# SCH_GroeiAcademie-Stimulus-Hardware-Shie.net
KiCad netlist of a schematic drawn in EasyEDA
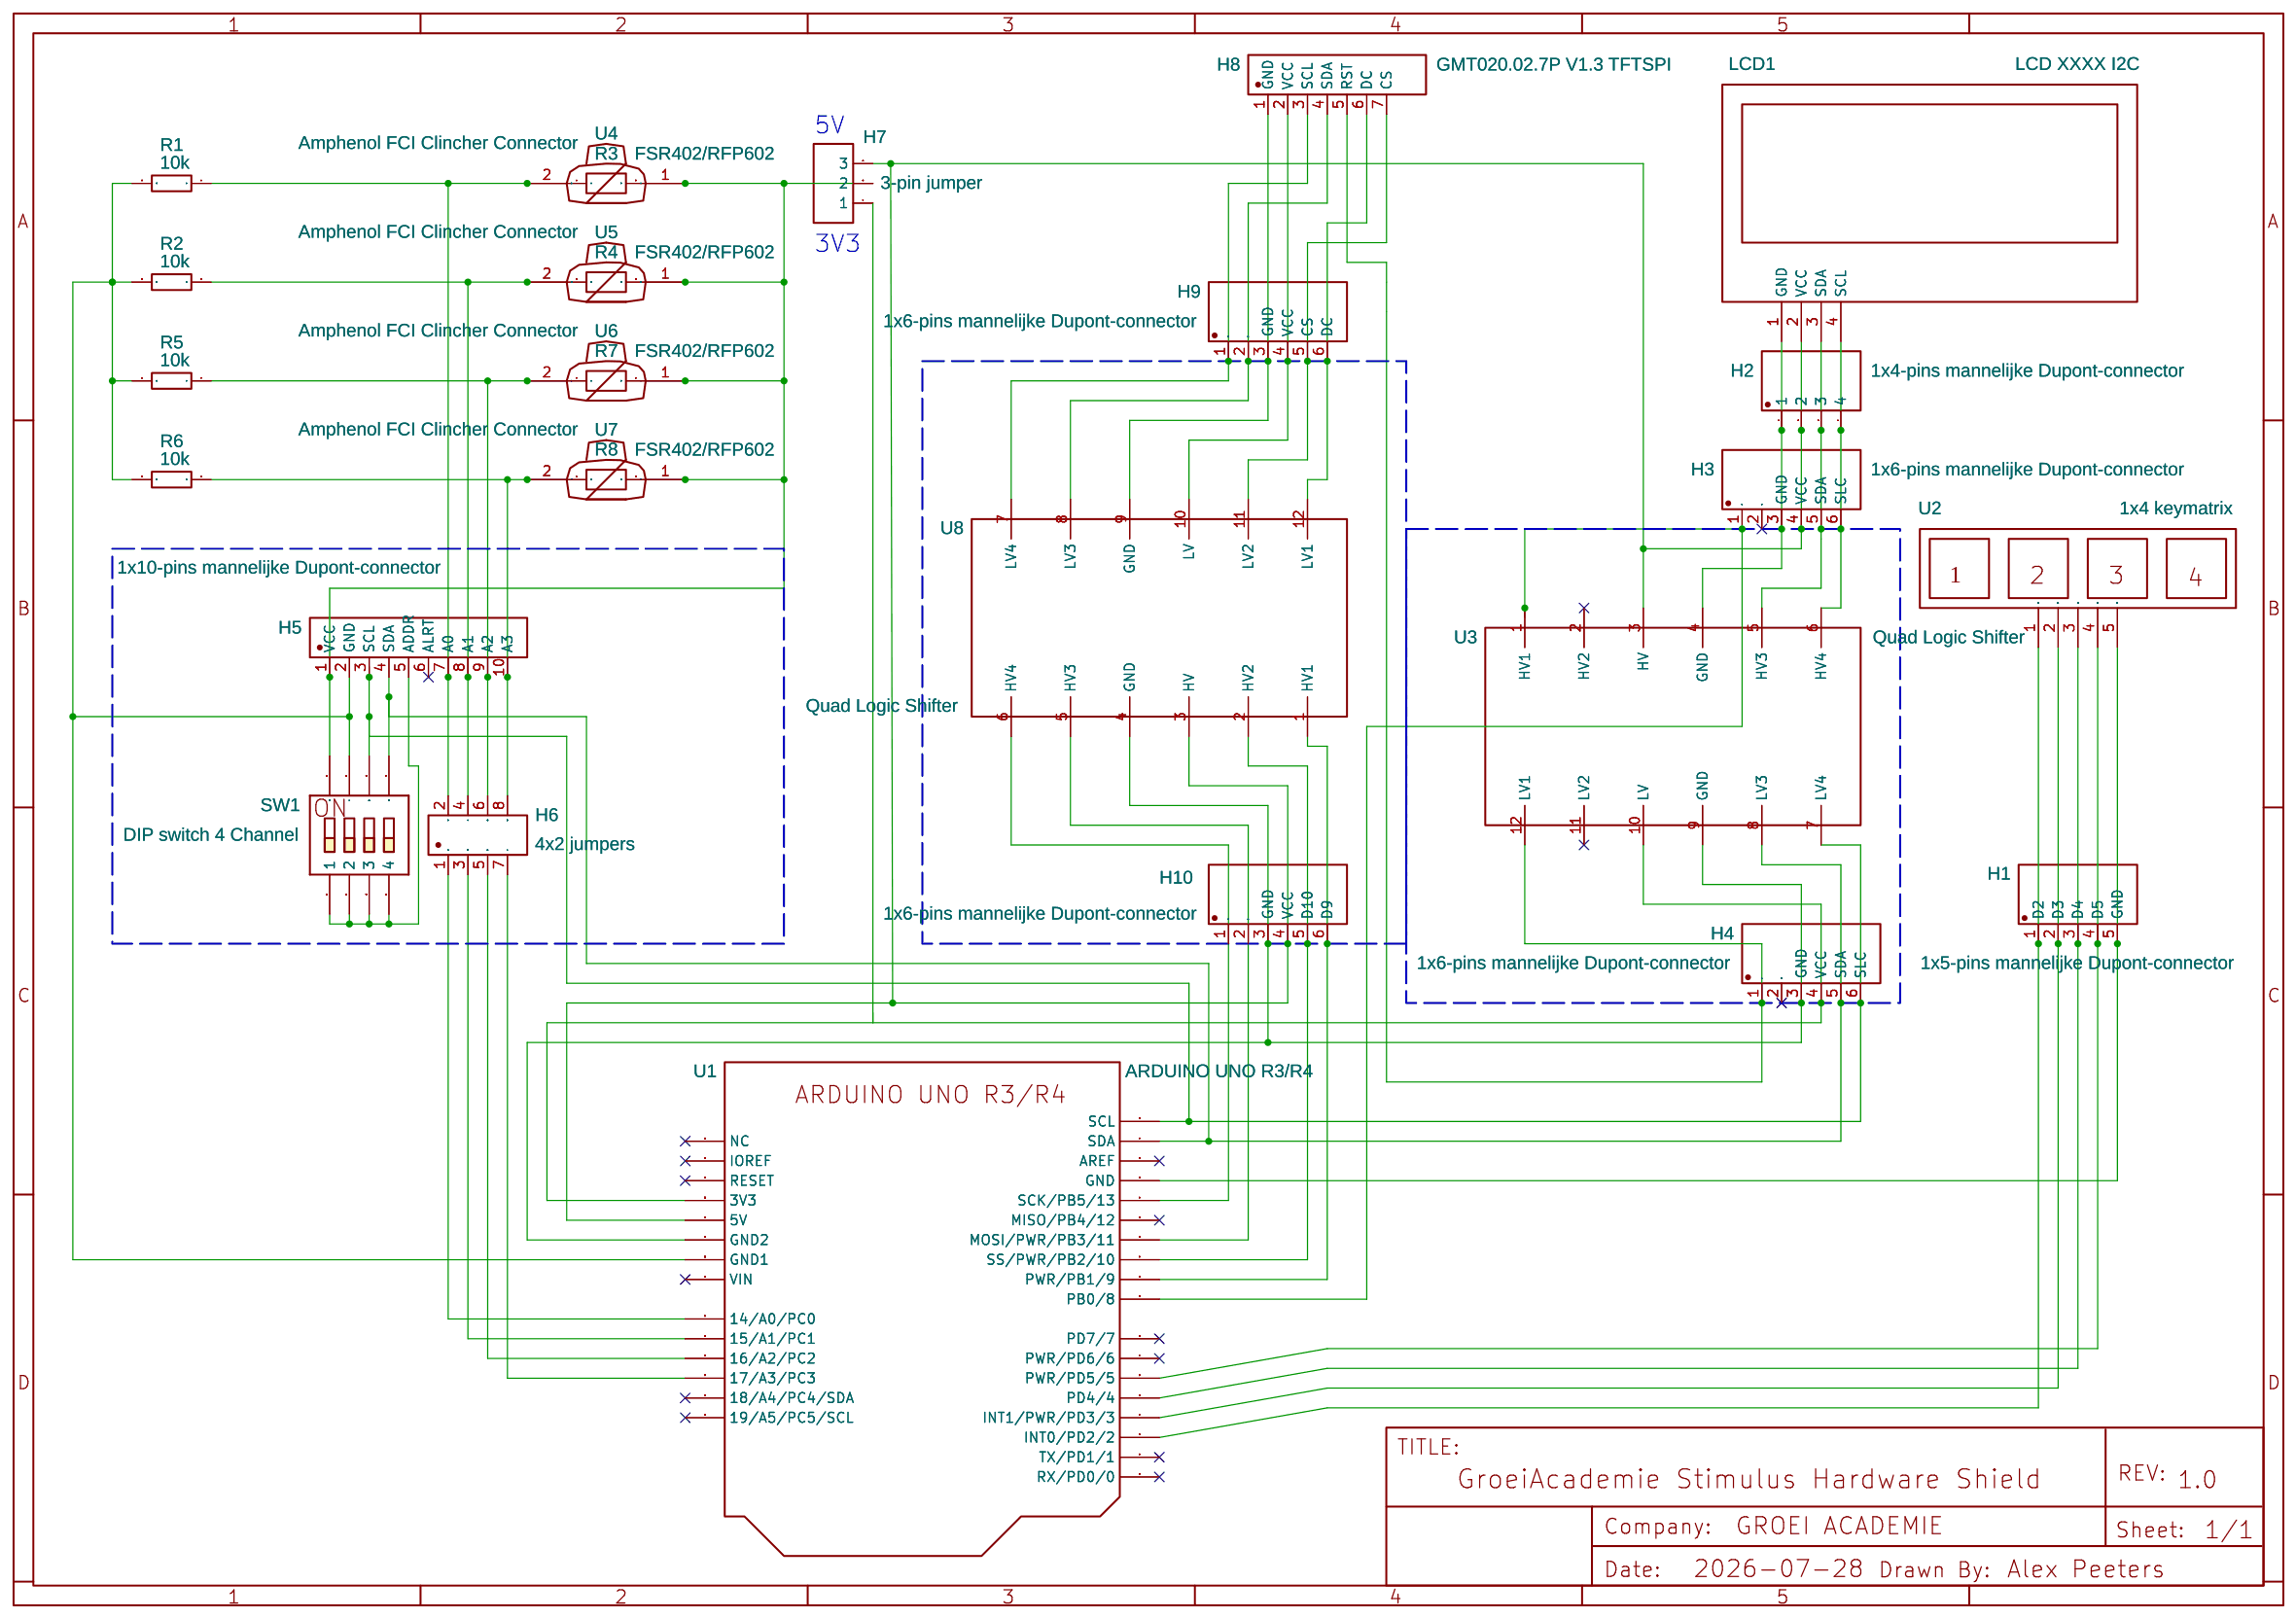
[diagram p0: schematic sheet]

(export (version "E")
  (design (tool "Eeschema 10.0.6"))
  (components
    (comp (ref "H1")
      (value "1x5-pins mannelijke Dupont-connector")
      (fields (field (name "Manufacturer Part") "B-2100S05P-A110") (field (name "Manufacturer") "Ckmtw(灿科盟)"))
      (libsource (lib "") (part "210S-1*5P L=11.6MMGold-plated black"))
    )
    (comp (ref "H2")
      (value "1x4-pins mannelijke Dupont-connector")
      (fields (field (name "Manufacturer Part") "B-2100S04P-A110") (field (name "Manufacturer") "Ckmtw(灿科盟)"))
      (libsource (lib "") (part "Header-Male-2.54_1x4"))
    )
    (comp (ref "H3")
      (value "1x6-pins mannelijke Dupont-connector")
      (fields (field (name "Manufacturer Part") "B-2100S06P-A110") (field (name "Manufacturer") "Ckmtw(灿科盟)"))
      (libsource (lib "") (part "210S-1*6P L=11.6MMGold-plated black_2"))
    )
    (comp (ref "H4")
      (value "1x6-pins mannelijke Dupont-connector")
      (fields (field (name "Manufacturer Part") "B-2100S06P-A110") (field (name "Manufacturer") "Ckmtw(灿科盟)"))
      (libsource (lib "") (part "210S-1*6P L=11.6MMGold-plated black_2"))
    )
    (comp (ref "H5")
      (value "1x10-pins mannelijke Dupont-connector")
      (fields (field (name "Manufacturer Part") "2.54-1*10") (field (name "Manufacturer") "ZHOURI(洲日)"))
      (libsource (lib "") (part "2.54-1*10"))
    )
    (comp (ref "H6")
      (value "4x2 jumpers")
      (fields (field (name "Manufacturer Part") "2.54-2*4P立贴针") (field (name "Manufacturer") "BOOMELE(博穆精密)"))
      (libsource (lib "") (part "2.54-2*4P立贴针"))
    )
    (comp (ref "H7") (value "3-pin jumper") (libsource (lib "") (part "HDR-F-2.54_1x3")))
    (comp (ref "H8")
      (value "GMT020.02.7P V1.3 TFTSPI")
      (fields (field (name "Manufacturer Part") "HDR-M-L12-3+4-1x8P-2.54"))
      (libsource (lib "") (part "PZ254R-11-08P"))
    )
    (comp (ref "H9")
      (value "1x6-pins mannelijke Dupont-connector")
      (fields (field (name "Manufacturer Part") "B-2100S06P-A110") (field (name "Manufacturer") "Ckmtw(灿科盟)"))
      (libsource (lib "") (part "210S-1*6P L=11.6MMGold-plated black_1"))
    )
    (comp (ref "H10")
      (value "1x6-pins mannelijke Dupont-connector")
      (fields (field (name "Manufacturer Part") "B-2100S06P-A110") (field (name "Manufacturer") "Ckmtw(灿科盟)"))
      (libsource (lib "") (part "210S-1*6P L=11.6MMGold-plated black"))
    )
    (comp (ref "LCD1") (value "LCD XXXX I2C") (libsource (lib "") (part "I2CLCD16X2_N")))
    (comp (ref "R1")
      (value "10k")
      (fields (field (name "Manufacturer") "Made in China"))
      (libsource (lib "") (part "330Ω (331) ±5%"))
    )
    (comp (ref "R2")
      (value "10k")
      (fields (field (name "Manufacturer") "Made in China"))
      (libsource (lib "") (part "330Ω (331) ±5%"))
    )
    (comp (ref "R3") (value "FSR402/RFP602") (libsource (lib "") (part "FSR402-OPCION1")))
    (comp (ref "R4") (value "FSR402/RFP602") (libsource (lib "") (part "FSR402-OPCION1")))
    (comp (ref "R5")
      (value "10k")
      (fields (field (name "Manufacturer") "Made in China"))
      (libsource (lib "") (part "330Ω (331) ±5%"))
    )
    (comp (ref "R6")
      (value "10k")
      (fields (field (name "Manufacturer") "Made in China"))
      (libsource (lib "") (part "330Ω (331) ±5%"))
    )
    (comp (ref "R7") (value "FSR402/RFP602") (libsource (lib "") (part "FSR402-OPCION1")))
    (comp (ref "R8") (value "FSR402/RFP602") (libsource (lib "") (part "FSR402-OPCION1")))
    (comp (ref "SW1")
      (value "DIP switch 4 Channel")
      (fields
        (field (name "Manufacturer Part") "DIP switch,Dip Switch,DSWB04LHGET")
        (field (name "Manufacturer") "KE")
      )
      (libsource (lib "") (part "DIP switch 4 Channel"))
    )
    (comp (ref "U1") (value "ARDUINO UNO R3/R4") (libsource (lib "") (part "ARDUINO UNO r3")))
    (comp (ref "U2") (value "1x4 keymatrix") (libsource (lib "") (part "Клавиатура 4*4")))
    (comp (ref "U3") (value "Quad Logic Shifter") (libsource (lib "") (part "Quad Logic Shifter")))
    (comp (ref "U4")
      (value "Amphenol FCI Clincher Connector")
      (fields (field (name "Manufacturer Part") "AT04-2P-BM02") (field (name "Manufacturer") "Amphenol"))
      (libsource (lib "") (part "AT04-2P"))
    )
    (comp (ref "U5")
      (value "Amphenol FCI Clincher Connector")
      (fields (field (name "Manufacturer Part") "AT04-2P-BM02") (field (name "Manufacturer") "Amphenol"))
      (libsource (lib "") (part "AT04-2P"))
    )
    (comp (ref "U6")
      (value "Amphenol FCI Clincher Connector")
      (fields (field (name "Manufacturer Part") "AT04-2P-BM02") (field (name "Manufacturer") "Amphenol"))
      (libsource (lib "") (part "AT04-2P"))
    )
    (comp (ref "U7")
      (value "Amphenol FCI Clincher Connector")
      (fields (field (name "Manufacturer Part") "AT04-2P-BM02") (field (name "Manufacturer") "Amphenol"))
      (libsource (lib "") (part "AT04-2P"))
    )
    (comp (ref "U8") (value "Quad Logic Shifter") (libsource (lib "") (part "Quad Logic Shifter_1")))
  )
  (nets
    (net (code "1") (name "Net-(H1-D2)") (class "Default")
      (node (ref "H1") (pin "1") (pinfunction "D2_1") (pintype "unspecified"))
      (node (ref "U1") (pin "3") (pinfunction "INT0/PD2/2_3") (pintype "unspecified"))
      (node (ref "U2") (pin "1") (pinfunction "C1_1") (pintype "unspecified"))
    )
    (net (code "2") (name "Net-(H1-D3)") (class "Default")
      (node (ref "H1") (pin "2") (pinfunction "D3_2") (pintype "unspecified"))
      (node (ref "U1") (pin "4") (pinfunction "INT1/PWR/PD3/3_4") (pintype "unspecified"))
      (node (ref "U2") (pin "2") (pinfunction "C2_2") (pintype "unspecified"))
    )
    (net (code "3") (name "Net-(H1-D4)") (class "Default")
      (node (ref "H1") (pin "3") (pinfunction "D4_3") (pintype "unspecified"))
      (node (ref "U1") (pin "5") (pinfunction "PD4/4_5") (pintype "unspecified"))
      (node (ref "U2") (pin "3") (pinfunction "C3_3") (pintype "unspecified"))
    )
    (net (code "4") (name "Net-(H1-D5)") (class "Default")
      (node (ref "H1") (pin "4") (pinfunction "D5_4") (pintype "unspecified"))
      (node (ref "U1") (pin "6") (pinfunction "PWR/PD5/5_6") (pintype "unspecified"))
      (node (ref "U2") (pin "4") (pinfunction "R1_4") (pintype "unspecified"))
    )
    (net (code "5") (name "Net-(H1-GND)") (class "Default")
      (node (ref "H1") (pin "5") (pinfunction "GND_5") (pintype "unspecified"))
      (node (ref "U1") (pin "15") (pinfunction "GND_15") (pintype "passive"))
      (node (ref "U2") (pin "5") (pinfunction "R2_5") (pintype "unspecified"))
    )
    (net (code "6") (name "Net-(H3-GND)") (class "Default")
      (node (ref "H2") (pin "1") (pinfunction "1_1") (pintype "unspecified"))
      (node (ref "H3") (pin "3") (pinfunction "GND_3") (pintype "unspecified"))
      (node (ref "LCD1") (pin "1") (pinfunction "GND_1") (pintype "unspecified"))
      (node (ref "U3") (pin "4") (pinfunction "GND_4") (pintype "unspecified"))
    )
    (net (code "7") (name "Net-(H3-SDA)") (class "Default")
      (node (ref "H2") (pin "3") (pinfunction "3_3") (pintype "unspecified"))
      (node (ref "H3") (pin "5") (pinfunction "SDA_5") (pintype "unspecified"))
      (node (ref "LCD1") (pin "3") (pinfunction "SDA_3") (pintype "unspecified"))
      (node (ref "U3") (pin "5") (pinfunction "HV3_5") (pintype "unspecified"))
    )
    (net (code "8") (name "Net-(H3-SLC)") (class "Default")
      (node (ref "H2") (pin "4") (pinfunction "4_4") (pintype "unspecified"))
      (node (ref "H3") (pin "6") (pinfunction "SLC_6") (pintype "unspecified"))
      (node (ref "LCD1") (pin "4") (pinfunction "SCL_4") (pintype "unspecified"))
      (node (ref "U3") (pin "6") (pinfunction "HV4_6") (pintype "unspecified"))
    )
    (net (code "9") (name "Net-(H4-SDA)") (class "Default")
      (node (ref "H4") (pin "5") (pinfunction "SDA_5") (pintype "unspecified"))
      (node (ref "H5") (pin "4") (pinfunction "SDA_4") (pintype "unspecified"))
      (node (ref "SW1") (pin "4I") (pinfunction "5_4I") (pintype "input"))
      (node (ref "U1") (pin "17") (pinfunction "SDA_17") (pintype "unspecified"))
      (node (ref "U3") (pin "8") (pinfunction "LV3_8") (pintype "unspecified"))
    )
    (net (code "10") (name "Net-(H4-SLC)") (class "Default")
      (node (ref "H4") (pin "6") (pinfunction "SLC_6") (pintype "unspecified"))
      (node (ref "H5") (pin "3") (pinfunction "SCL_3") (pintype "unspecified"))
      (node (ref "SW1") (pin "3I") (pinfunction "6_3I") (pintype "input"))
      (node (ref "U1") (pin "18") (pinfunction "SCL_18") (pintype "unspecified"))
      (node (ref "U3") (pin "7") (pinfunction "LV4_7") (pintype "unspecified"))
    )
    (net (code "11") (name "Net-(H4-VCC)") (class "Default")
      (node (ref "H4") (pin "4") (pinfunction "VCC_4") (pintype "unspecified"))
      (node (ref "U1") (pin "29") (pinfunction "3V3_29") (pintype "passive"))
      (node (ref "U3") (pin "10") (pinfunction "LV_10") (pintype "unspecified"))
    )
    (net (code "12") (name "Net-(H5-A0)") (class "Default")
      (node (ref "H5") (pin "7") (pinfunction "A0_7") (pintype "unspecified"))
      (node (ref "H6") (pin "2") (pinfunction "2_2") (pintype "unspecified"))
      (node (ref "R1") (pin "1") (pinfunction "1_1") (pintype "unspecified"))
      (node (ref "R3") (pin "1") (pinfunction "1_1") (pintype "unspecified"))
      (node (ref "U4") (pin "2") (pinfunction "2_2") (pintype "unspecified"))
    )
    (net (code "13") (name "Net-(H5-A1)") (class "Default")
      (node (ref "H5") (pin "8") (pinfunction "A1_8") (pintype "unspecified"))
      (node (ref "H6") (pin "4") (pinfunction "4_4") (pintype "unspecified"))
      (node (ref "R2") (pin "1") (pinfunction "1_1") (pintype "unspecified"))
      (node (ref "R4") (pin "1") (pinfunction "1_1") (pintype "unspecified"))
      (node (ref "U5") (pin "2") (pinfunction "2_2") (pintype "unspecified"))
    )
    (net (code "14") (name "Net-(H5-A2)") (class "Default")
      (node (ref "H5") (pin "9") (pinfunction "A2_9") (pintype "unspecified"))
      (node (ref "H6") (pin "6") (pinfunction "6_6") (pintype "unspecified"))
      (node (ref "R5") (pin "1") (pinfunction "1_1") (pintype "unspecified"))
      (node (ref "R7") (pin "1") (pinfunction "1_1") (pintype "unspecified"))
      (node (ref "U6") (pin "2") (pinfunction "2_2") (pintype "unspecified"))
    )
    (net (code "15") (name "Net-(H5-A3)") (class "Default")
      (node (ref "H5") (pin "10") (pinfunction "A3_10") (pintype "unspecified"))
      (node (ref "H6") (pin "8") (pinfunction "8_8") (pintype "unspecified"))
      (node (ref "R6") (pin "1") (pinfunction "1_1") (pintype "unspecified"))
      (node (ref "R8") (pin "1") (pinfunction "1_1") (pintype "unspecified"))
      (node (ref "U7") (pin "2") (pinfunction "2_2") (pintype "unspecified"))
    )
    (net (code "16") (name "Net-(H5-ADDR)") (class "Default")
      (node (ref "H5") (pin "5") (pinfunction "ADDR_5") (pintype "unspecified"))
      (node (ref "SW1") (pin "1O") (pinfunction "1_1O") (pintype "input"))
      (node (ref "SW1") (pin "2O") (pinfunction "2_2O") (pintype "input"))
      (node (ref "SW1") (pin "3O") (pinfunction "3_3O") (pintype "input"))
      (node (ref "SW1") (pin "4O") (pinfunction "4_4O") (pintype "input"))
    )
    (net (code "17") (name "Net-(H5-GND)") (class "Default")
      (node (ref "H5") (pin "2") (pinfunction "GND_2") (pintype "unspecified"))
      (node (ref "R1") (pin "2") (pinfunction "2_2") (pintype "unspecified"))
      (node (ref "R2") (pin "2") (pinfunction "2_2") (pintype "unspecified"))
      (node (ref "R5") (pin "2") (pinfunction "2_2") (pintype "unspecified"))
      (node (ref "R6") (pin "2") (pinfunction "2_2") (pintype "unspecified"))
      (node (ref "SW1") (pin "2I") (pinfunction "7_2I") (pintype "input"))
      (node (ref "U1") (pin "26") (pinfunction "GND1_26") (pintype "passive"))
    )
    (net (code "18") (name "Net-(H5-VCC)") (class "Default")
      (node (ref "H5") (pin "1") (pinfunction "VCC_1") (pintype "unspecified"))
      (node (ref "H7") (pin "2") (pinfunction "2_2") (pintype "input"))
      (node (ref "R3") (pin "2") (pinfunction "2_2") (pintype "unspecified"))
      (node (ref "R4") (pin "2") (pinfunction "2_2") (pintype "unspecified"))
      (node (ref "R7") (pin "2") (pinfunction "2_2") (pintype "unspecified"))
      (node (ref "R8") (pin "2") (pinfunction "2_2") (pintype "unspecified"))
      (node (ref "SW1") (pin "1I") (pinfunction "8_1I") (pintype "input"))
      (node (ref "U4") (pin "1") (pinfunction "1_1") (pintype "unspecified"))
      (node (ref "U5") (pin "1") (pinfunction "1_1") (pintype "unspecified"))
      (node (ref "U6") (pin "1") (pinfunction "1_1") (pintype "unspecified"))
      (node (ref "U7") (pin "1") (pinfunction "1_1") (pintype "unspecified"))
    )
    (net (code "19") (name "Net-(H8-CS)") (class "Default")
      (node (ref "H8") (pin "7") (pinfunction "CS_7") (pintype "unspecified"))
      (node (ref "H9") (pin "5") (pinfunction "CS_5") (pintype "unspecified"))
      (node (ref "U8") (pin "11") (pinfunction "LV2_11") (pintype "unspecified"))
    )
    (net (code "20") (name "Net-(H8-DC)") (class "Default")
      (node (ref "H8") (pin "6") (pinfunction "DC_6") (pintype "unspecified"))
      (node (ref "H9") (pin "6") (pinfunction "DC_6") (pintype "unspecified"))
      (node (ref "U8") (pin "12") (pinfunction "LV1_12") (pintype "unspecified"))
    )
    (net (code "21") (name "Net-(H8-GND)") (class "Default")
      (node (ref "H8") (pin "1") (pinfunction "GND_1") (pintype "unspecified"))
      (node (ref "H9") (pin "3") (pinfunction "GND_3") (pintype "unspecified"))
      (node (ref "U8") (pin "9") (pinfunction "GND_9") (pintype "unspecified"))
    )
    (net (code "22") (name "Net-(H8-RST)") (class "Default")
      (node (ref "H4") (pin "1") (pinfunction "1_1") (pintype "unspecified"))
      (node (ref "H8") (pin "5") (pinfunction "RST_5") (pintype "unspecified"))
      (node (ref "U3") (pin "12") (pinfunction "LV1_12") (pintype "unspecified"))
    )
    (net (code "23") (name "Net-(H8-SCL)") (class "Default")
      (node (ref "H8") (pin "3") (pinfunction "SCL_3") (pintype "unspecified"))
      (node (ref "H9") (pin "1") (pinfunction "1_1") (pintype "unspecified"))
      (node (ref "U8") (pin "7") (pinfunction "LV4_7") (pintype "unspecified"))
    )
    (net (code "24") (name "Net-(H8-SDA)") (class "Default")
      (node (ref "H8") (pin "4") (pinfunction "SDA_4") (pintype "unspecified"))
      (node (ref "H9") (pin "2") (pinfunction "2_2") (pintype "unspecified"))
      (node (ref "U8") (pin "8") (pinfunction "LV3_8") (pintype "unspecified"))
    )
    (net (code "25") (name "Net-(H8-VCC)") (class "Default")
      (node (ref "H8") (pin "2") (pinfunction "VCC_2") (pintype "unspecified"))
      (node (ref "H9") (pin "4") (pinfunction "VCC_4") (pintype "unspecified"))
      (node (ref "U8") (pin "10") (pinfunction "LV_10") (pintype "unspecified"))
    )
    (net (code "26") (name "Net-(H10-D9)") (class "Default")
      (node (ref "H10") (pin "6") (pinfunction "D9_6") (pintype "unspecified"))
      (node (ref "U1") (pin "10") (pinfunction "PWR/PB1/9_10") (pintype "unspecified"))
      (node (ref "U8") (pin "1") (pinfunction "HV1_1") (pintype "unspecified"))
    )
    (net (code "27") (name "Net-(H10-D10)") (class "Default")
      (node (ref "H10") (pin "5") (pinfunction "D10_5") (pintype "unspecified"))
      (node (ref "U1") (pin "11") (pinfunction "SS/PWR/PB2/10_11") (pintype "unspecified"))
      (node (ref "U8") (pin "2") (pinfunction "HV2_2") (pintype "unspecified"))
    )
    (net (code "28") (name "Net-(H10-GND)") (class "Default")
      (node (ref "H10") (pin "3") (pinfunction "GND_3") (pintype "unspecified"))
      (node (ref "H4") (pin "3") (pinfunction "GND_3") (pintype "unspecified"))
      (node (ref "U1") (pin "27") (pinfunction "GND2_27") (pintype "passive"))
      (node (ref "U3") (pin "9") (pinfunction "GND_9") (pintype "unspecified"))
      (node (ref "U8") (pin "4") (pinfunction "GND_4") (pintype "unspecified"))
    )
    (net (code "29") (name "Net-(H10-VCC)") (class "Default")
      (node (ref "H10") (pin "4") (pinfunction "VCC_4") (pintype "unspecified"))
      (node (ref "H2") (pin "2") (pinfunction "2_2") (pintype "unspecified"))
      (node (ref "H3") (pin "4") (pinfunction "VCC_4") (pintype "unspecified"))
      (node (ref "H7") (pin "3") (pinfunction "3_3") (pintype "input"))
      (node (ref "LCD1") (pin "2") (pinfunction "VCC_2") (pintype "unspecified"))
      (node (ref "U1") (pin "28") (pinfunction "5V_28") (pintype "passive"))
      (node (ref "U3") (pin "3") (pinfunction "HV_3") (pintype "unspecified"))
      (node (ref "U8") (pin "3") (pinfunction "HV_3") (pintype "unspecified"))
    )
    (net (code "30") (name "Net-(U1-14{slash}A0{slash}PC0)") (class "Default")
      (node (ref "H6") (pin "1") (pinfunction "1_1") (pintype "unspecified"))
      (node (ref "U1") (pin "24") (pinfunction "14/A0/PC0_24") (pintype "unspecified"))
    )
    (net (code "31") (name "Net-(U1-15{slash}A1{slash}PC1)") (class "Default")
      (node (ref "H6") (pin "3") (pinfunction "3_3") (pintype "unspecified"))
      (node (ref "U1") (pin "23") (pinfunction "15/A1/PC1_23") (pintype "unspecified"))
    )
    (net (code "32") (name "Net-(U1-16{slash}A2{slash}PC2)") (class "Default")
      (node (ref "H6") (pin "5") (pinfunction "5_5") (pintype "unspecified"))
      (node (ref "U1") (pin "22") (pinfunction "16/A2/PC2_22") (pintype "unspecified"))
    )
    (net (code "33") (name "Net-(U1-17{slash}A3{slash}PC3)") (class "Default")
      (node (ref "H6") (pin "7") (pinfunction "7_7") (pintype "unspecified"))
      (node (ref "U1") (pin "21") (pinfunction "17/A3/PC3_21") (pintype "unspecified"))
    )
    (net (code "34") (name "Net-(U1-MOSI{slash}PWR{slash}PB3{slash}11)") (class "Default")
      (node (ref "H10") (pin "2") (pinfunction "2_2") (pintype "unspecified"))
      (node (ref "U1") (pin "12") (pinfunction "MOSI/PWR/PB3/11_12") (pintype "unspecified"))
    )
    (net (code "35") (name "Net-(U1-PB0{slash}8)") (class "Default")
      (node (ref "H3") (pin "1") (pinfunction "1_1") (pintype "unspecified"))
      (node (ref "U1") (pin "9") (pinfunction "PB0/8_9") (pintype "unspecified"))
      (node (ref "U3") (pin "1") (pinfunction "HV1_1") (pintype "unspecified"))
    )
    (net (code "36") (name "Net-(U1-SCK{slash}PB5{slash}13)") (class "Default")
      (node (ref "H10") (pin "1") (pinfunction "1_1") (pintype "unspecified"))
      (node (ref "U1") (pin "14") (pinfunction "SCK/PB5/13_14") (pintype "unspecified"))
    )
    (net (code "37") (name "unconnected-(H3-Pad2)") (class "Default")
      (node (ref "H3") (pin "2") (pinfunction "2_2") (pintype "unspecified+no_connect"))
    )
    (net (code "38") (name "unconnected-(H4-Pad2)") (class "Default")
      (node (ref "H4") (pin "2") (pinfunction "2_2") (pintype "unspecified+no_connect"))
    )
    (net (code "39") (name "unconnected-(H5-ALRT-Pad6)") (class "Default")
      (node (ref "H5") (pin "6") (pinfunction "ALRT_6") (pintype "unspecified+no_connect"))
    )
    (net (code "40") (name "unconnected-(H7-Pad1)") (class "Default")
      (node (ref "H7") (pin "1") (pinfunction "1_1") (pintype "input"))
    )
    (net (code "41") (name "unconnected-(U1-18{slash}A4{slash}PC4{slash}SDA-Pad20)") (class "Default")
      (node (ref "U1") (pin "20") (pinfunction "18/A4/PC4/SDA_20") (pintype "unspecified+no_connect"))
    )
    (net (code "42") (name "unconnected-(U1-19{slash}A5{slash}PC5{slash}SCL-Pad19)") (class "Default")
      (node (ref "U1") (pin "19") (pinfunction "19/A5/PC5/SCL_19") (pintype "unspecified+no_connect"))
    )
    (net (code "43") (name "unconnected-(U1-AREF-Pad16)") (class "Default")
      (node (ref "U1") (pin "16") (pinfunction "AREF_16") (pintype "unspecified+no_connect"))
    )
    (net (code "44") (name "unconnected-(U1-IOREF-Pad31)") (class "Default")
      (node (ref "U1") (pin "31") (pinfunction "IOREF_31") (pintype "unspecified+no_connect"))
    )
    (net (code "45") (name "unconnected-(U1-MISO{slash}PB4{slash}12-Pad13)") (class "Default")
      (node (ref "U1") (pin "13") (pinfunction "MISO/PB4/12_13") (pintype "unspecified+no_connect"))
    )
    (net (code "46") (name "unconnected-(U1-NC-Pad32)") (class "Default")
      (node (ref "U1") (pin "32") (pinfunction "NC_32") (pintype "unspecified+no_connect"))
    )
    (net (code "47") (name "unconnected-(U1-PD7{slash}7-Pad8)") (class "Default")
      (node (ref "U1") (pin "8") (pinfunction "PD7/7_8") (pintype "unspecified+no_connect"))
    )
    (net (code "48") (name "unconnected-(U1-PWR{slash}PD6{slash}6-Pad7)") (class "Default")
      (node (ref "U1") (pin "7") (pinfunction "PWR/PD6/6_7") (pintype "unspecified+no_connect"))
    )
    (net (code "49") (name "unconnected-(U1-RESET-Pad30)") (class "Default")
      (node (ref "U1") (pin "30") (pinfunction "RESET_30") (pintype "unspecified+no_connect"))
    )
    (net (code "50") (name "unconnected-(U1-RX{slash}PD0{slash}0-Pad1)") (class "Default")
      (node (ref "U1") (pin "1") (pinfunction "RX/PD0/0_1") (pintype "unspecified+no_connect"))
    )
    (net (code "51") (name "unconnected-(U1-TX{slash}PD1{slash}1-Pad2)") (class "Default")
      (node (ref "U1") (pin "2") (pinfunction "TX/PD1/1_2") (pintype "unspecified+no_connect"))
    )
    (net (code "52") (name "unconnected-(U1-VIN-Pad25)") (class "Default")
      (node (ref "U1") (pin "25") (pinfunction "VIN_25") (pintype "passive+no_connect"))
    )
    (net (code "53") (name "unconnected-(U3-HV2-Pad2)") (class "Default")
      (node (ref "U3") (pin "2") (pinfunction "HV2_2") (pintype "unspecified+no_connect"))
    )
    (net (code "54") (name "unconnected-(U3-LV2-Pad11)") (class "Default")
      (node (ref "U3") (pin "11") (pinfunction "LV2_11") (pintype "unspecified+no_connect"))
    )
    (net (code "55") (name "unconnected-(U8-HV3-Pad5)") (class "Default")
      (node (ref "U8") (pin "5") (pinfunction "HV3_5") (pintype "unspecified"))
    )
    (net (code "56") (name "unconnected-(U8-HV4-Pad6)") (class "Default")
      (node (ref "U8") (pin "6") (pinfunction "HV4_6") (pintype "unspecified"))
    )
  )
)
